# openSX70-dongle_v4-push-MINI.net
KiCad netlist of a schematic drawn in EAGLE
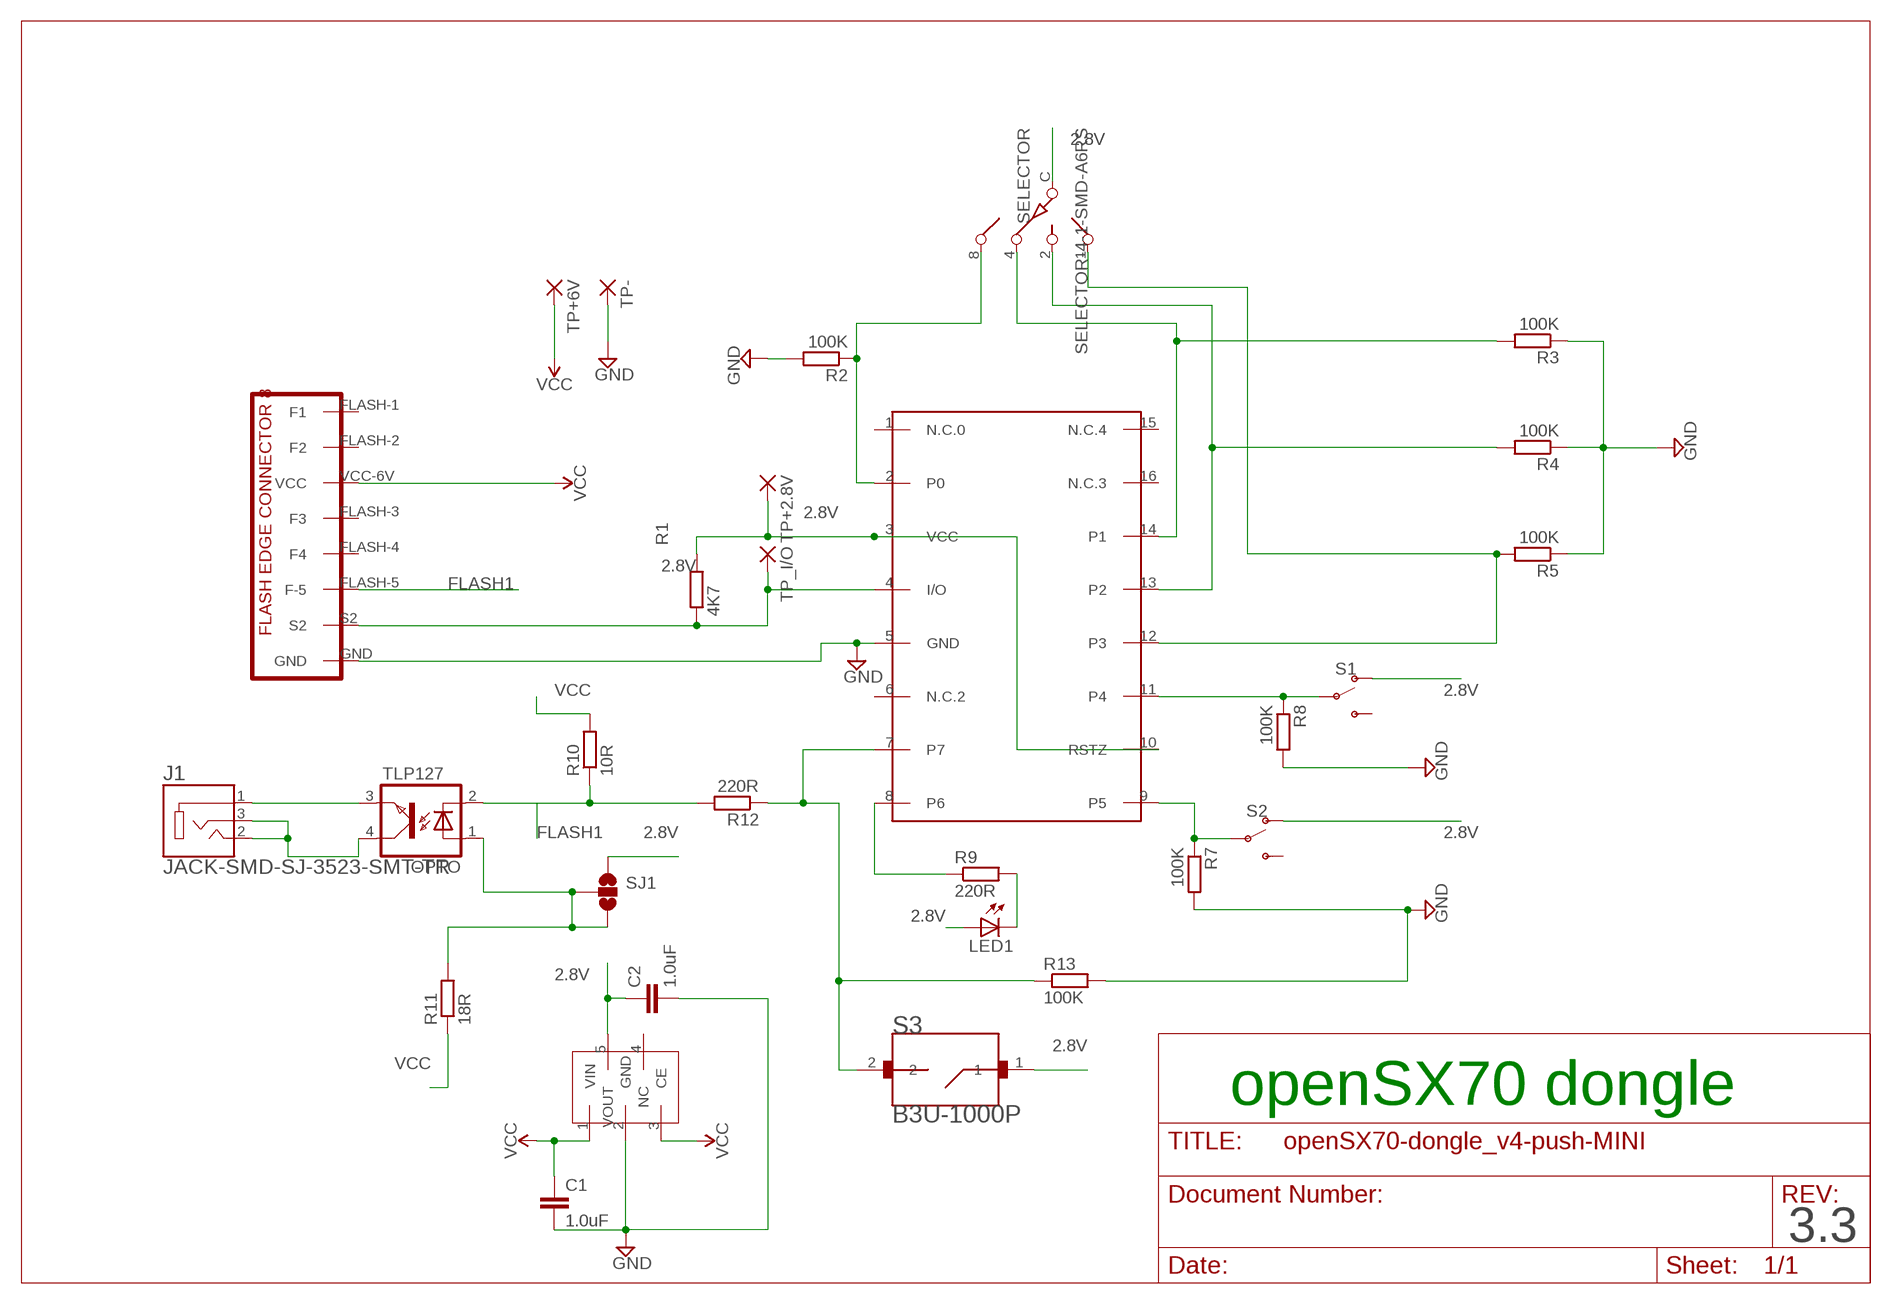
[diagram p0: schematic, sheet 1]

(export (version "E")
  (design (tool "Eeschema 10.0.6"))
  (components
    (comp (ref "C1")
      (value "1.0uF")
      (footprint "eagle-import:C0603")
      (libsource (lib "eagle-import") (part "C-EUC0603"))
    )
    (comp (ref "C2")
      (value "1.0uF")
      (footprint "eagle-import:C0603")
      (libsource (lib "eagle-import") (part "C-EUC0603"))
    )
    (comp (ref "DS2408")
      (value "DS2408")
      (footprint "eagle-import:SO16")
      (libsource (lib "eagle-import") (part "DS2408"))
    )
    (comp (ref "J1")
      (value "JACK-SMD-SJ-3523-SMT-TR")
      (footprint "eagle-import:CUI_SJ-3523-SMT-TR")
      (fields (field (name "MF") "CUI Inc.") (field (name "MP") "SJ-3523-SMT-TR"))
      (libsource (lib "eagle-import") (part "JACK-SMD-SJ-3523-SMT-TR"))
    )
    (comp (ref "LED1")
      (value "LED3MM")
      (footprint "eagle-import:LED3MM")
      (libsource (lib "eagle-import") (part "LED3MM"))
    )
    (comp (ref "OPTO")
      (value "TLP127")
      (footprint "eagle-import:SO-4")
      (libsource (lib "eagle-import") (part "TLP127"))
    )
    (comp (ref "R1")
      (value "4K7")
      (footprint "eagle-import:R0603")
      (libsource (lib "eagle-import") (part "R-EU_R0603"))
    )
    (comp (ref "R2")
      (value "100K")
      (footprint "eagle-import:R0603")
      (libsource (lib "eagle-import") (part "R-EU_R0603"))
    )
    (comp (ref "R3")
      (value "100K")
      (footprint "eagle-import:R0603")
      (libsource (lib "eagle-import") (part "R-EU_R0603"))
    )
    (comp (ref "R4")
      (value "100K")
      (footprint "eagle-import:R0603")
      (libsource (lib "eagle-import") (part "R-EU_R0603"))
    )
    (comp (ref "R5")
      (value "100K")
      (footprint "eagle-import:R0603")
      (libsource (lib "eagle-import") (part "R-EU_R0603"))
    )
    (comp (ref "R7")
      (value "100K")
      (footprint "eagle-import:R0603")
      (libsource (lib "eagle-import") (part "R-EU_R0603"))
    )
    (comp (ref "R8")
      (value "100K")
      (footprint "eagle-import:R0603")
      (libsource (lib "eagle-import") (part "R-EU_R0603"))
    )
    (comp (ref "R9")
      (value "220R")
      (footprint "eagle-import:R0603")
      (libsource (lib "eagle-import") (part "R-EU_R0603"))
    )
    (comp (ref "R10")
      (value "10R")
      (footprint "eagle-import:R0603")
      (libsource (lib "eagle-import") (part "resistor_348_R-EU_R0603"))
    )
    (comp (ref "R11")
      (value "18R")
      (footprint "eagle-import:R0603")
      (libsource (lib "eagle-import") (part "resistor_348_R-EU_R0603"))
    )
    (comp (ref "R12")
      (value "220R")
      (footprint "eagle-import:R0603")
      (libsource (lib "eagle-import") (part "R-EU_R0603"))
    )
    (comp (ref "R13")
      (value "100K")
      (footprint "eagle-import:R0603")
      (libsource (lib "eagle-import") (part "R-EU_R0603"))
    )
    (comp (ref "REG")
      (value "NCP4688")
      (footprint "eagle-import:SOT-23-5")
      (libsource (lib "eagle-import") (part "NCP4688"))
    )
    (comp (ref "S1")
      (value "SWITCH-SPDT-SMD-RIGHT-ANGLE")
      (footprint "eagle-import:SWITCH_SPST_SMD_A")
      (libsource (lib "eagle-import") (part "SWITCH-SPDT-SMD-RIGHT-ANGLE"))
    )
    (comp (ref "S2")
      (value "SWITCH-SPDT-SMD-RIGHT-ANGLE")
      (footprint "eagle-import:SWITCH_SPST_SMD_A")
      (libsource (lib "eagle-import") (part "SWITCH-SPDT-SMD-RIGHT-ANGLE"))
    )
    (comp (ref "S3")
      (value "B3U-1000P")
      (footprint "eagle-import:SW_B3U-1000P")
      (fields (field (name "MANUFACTURER") "Omron"))
      (libsource (lib "eagle-import") (part "B3U-1000P"))
    )
    (comp (ref "SELECTOR")
      (value "SELECTOR-4-1-SMD-A6RS")
      (footprint "eagle-import:A6RS-161RS")
      (libsource (lib "eagle-import") (part "SELECTOR-4-1-SMD-A6RS"))
    )
    (comp (ref "SJ1")
      (value "SOLDERJUMPER_2WAYS")
      (footprint "eagle-import:SJ_3")
      (libsource (lib "eagle-import") (part "SOLDERJUMPER_2WAYS"))
    )
    (comp (ref "TP+2.8V")
      (value "SMD2")
      (footprint "eagle-import:SMD1,27-2,54")
      (libsource (lib "eagle-import") (part "SMD2"))
    )
    (comp (ref "TP+6V")
      (value "SMD2")
      (footprint "eagle-import:SMD1,27-2,54")
      (libsource (lib "eagle-import") (part "SMD2"))
    )
    (comp (ref "TP-")
      (value "SMD2")
      (footprint "eagle-import:SMD1,27-2,54")
      (libsource (lib "eagle-import") (part "SMD2"))
    )
    (comp (ref "TP_I/O")
      (value "SMD2")
      (footprint "eagle-import:SMD1,27-2,54")
      (libsource (lib "eagle-import") (part "SMD2"))
    )
    (comp (ref "U$2")
      (value "SX70-FLASH-EDGE8-MALE-PROPER")
      (footprint "eagle-import:SX70-FLASH-EDGE8")
      (libsource (lib "eagle-import") (part "SX70-FLASH-EDGE8-MALE-PROPER"))
    )
  )
  (nets
    (net (code "1") (name "/2.8V") (class "Default")
      (node (ref "C2") (pin "1") (pinfunction "1_1") (pintype "passive"))
      (node (ref "DS2408") (pin "10") (pinfunction "RSTZ_10") (pintype "bidirectional"))
      (node (ref "DS2408") (pin "3") (pinfunction "VCC_3") (pintype "bidirectional"))
      (node (ref "LED1") (pin "A") (pinfunction "A_A") (pintype "passive"))
      (node (ref "R1") (pin "2") (pinfunction "2_2") (pintype "passive"))
      (node (ref "REG") (pin "5") (pinfunction "VOUT_5") (pintype "bidirectional"))
      (node (ref "S1") (pin "1") (pinfunction "O_1") (pintype "passive"))
      (node (ref "S2") (pin "1") (pinfunction "O_1") (pintype "passive"))
      (node (ref "S3") (pin "1") (pinfunction "1_1") (pintype "passive"))
      (node (ref "SELECTOR") (pin "C") (pinfunction "C_C") (pintype "passive"))
      (node (ref "SJ1") (pin "1") (pinfunction "1_1") (pintype "passive"))
      (node (ref "TP+2.8V") (pin "1") (pinfunction "P_1") (pintype "passive"))
    )
    (net (code "2") (name "/FLASH1") (class "Default")
      (node (ref "OPTO") (pin "1") (pinfunction "A_1") (pintype "passive"))
      (node (ref "OPTO") (pin "2") (pinfunction "C_2") (pintype "passive"))
      (node (ref "R10") (pin "1") (pinfunction "1_1") (pintype "passive"))
      (node (ref "R11") (pin "2") (pinfunction "2_2") (pintype "passive"))
      (node (ref "R12") (pin "2") (pinfunction "2_2") (pintype "passive"))
      (node (ref "SJ1") (pin "2") (pinfunction "2_2") (pintype "passive"))
      (node (ref "SJ1") (pin "3") (pinfunction "3_3") (pintype "passive"))
      (node (ref "U$2") (pin "FLASH-5") (pinfunction "F-5_FLASH-5") (pintype "bidirectional"))
    )
    (net (code "3") (name "GND") (class "Default")
      (node (ref "C1") (pin "2") (pinfunction "2_2") (pintype "passive"))
      (node (ref "C2") (pin "2") (pinfunction "2_2") (pintype "passive"))
      (node (ref "DS2408") (pin "5") (pinfunction "GND_5") (pintype "bidirectional"))
      (node (ref "R13") (pin "2") (pinfunction "2_2") (pintype "passive"))
      (node (ref "R2") (pin "2") (pinfunction "2_2") (pintype "passive"))
      (node (ref "R3") (pin "1") (pinfunction "1_1") (pintype "passive"))
      (node (ref "R4") (pin "1") (pinfunction "1_1") (pintype "passive"))
      (node (ref "R5") (pin "1") (pinfunction "1_1") (pintype "passive"))
      (node (ref "R7") (pin "2") (pinfunction "2_2") (pintype "passive"))
      (node (ref "R8") (pin "2") (pinfunction "2_2") (pintype "passive"))
      (node (ref "REG") (pin "2") (pinfunction "GND_2") (pintype "bidirectional"))
      (node (ref "TP-") (pin "1") (pinfunction "P_1") (pintype "passive"))
      (node (ref "U$2") (pin "GND") (pinfunction "GND_GND") (pintype "bidirectional"))
    )
    (net (code "4") (name "Net-(DS2408-I{slash}O)") (class "Default")
      (node (ref "DS2408") (pin "4") (pinfunction "I/O_4") (pintype "bidirectional"))
      (node (ref "R1") (pin "1") (pinfunction "1_1") (pintype "passive"))
      (node (ref "TP_I/O") (pin "1") (pinfunction "P_1") (pintype "passive"))
      (node (ref "U$2") (pin "S2") (pinfunction "S2_S2") (pintype "bidirectional"))
    )
    (net (code "5") (name "Net-(DS2408-P0)") (class "Default")
      (node (ref "DS2408") (pin "2") (pinfunction "P0_2") (pintype "bidirectional"))
      (node (ref "R2") (pin "1") (pinfunction "1_1") (pintype "passive"))
      (node (ref "SELECTOR") (pin "8") (pinfunction "8_8") (pintype "passive"))
    )
    (net (code "6") (name "Net-(DS2408-P1)") (class "Default")
      (node (ref "DS2408") (pin "14") (pinfunction "P1_14") (pintype "bidirectional"))
      (node (ref "R3") (pin "2") (pinfunction "2_2") (pintype "passive"))
      (node (ref "SELECTOR") (pin "4") (pinfunction "4_4") (pintype "passive"))
    )
    (net (code "7") (name "Net-(DS2408-P2)") (class "Default")
      (node (ref "DS2408") (pin "13") (pinfunction "P2_13") (pintype "bidirectional"))
      (node (ref "R4") (pin "2") (pinfunction "2_2") (pintype "passive"))
      (node (ref "SELECTOR") (pin "2") (pinfunction "2_2") (pintype "passive"))
    )
    (net (code "8") (name "Net-(DS2408-P3)") (class "Default")
      (node (ref "DS2408") (pin "12") (pinfunction "P3_12") (pintype "bidirectional"))
      (node (ref "R5") (pin "2") (pinfunction "2_2") (pintype "passive"))
      (node (ref "SELECTOR") (pin "1") (pinfunction "1_1") (pintype "passive"))
    )
    (net (code "9") (name "Net-(DS2408-P4)") (class "Default")
      (node (ref "DS2408") (pin "11") (pinfunction "P4_11") (pintype "bidirectional"))
      (node (ref "R8") (pin "1") (pinfunction "1_1") (pintype "passive"))
      (node (ref "S1") (pin "2") (pinfunction "P_2") (pintype "passive"))
    )
    (net (code "10") (name "Net-(DS2408-P5)") (class "Default")
      (node (ref "DS2408") (pin "9") (pinfunction "P5_9") (pintype "bidirectional"))
      (node (ref "R7") (pin "1") (pinfunction "1_1") (pintype "passive"))
      (node (ref "S2") (pin "2") (pinfunction "P_2") (pintype "passive"))
    )
    (net (code "11") (name "Net-(DS2408-P6)") (class "Default")
      (node (ref "DS2408") (pin "8") (pinfunction "P6_8") (pintype "bidirectional"))
      (node (ref "R9") (pin "1") (pinfunction "1_1") (pintype "passive"))
    )
    (net (code "12") (name "Net-(DS2408-P7)") (class "Default")
      (node (ref "DS2408") (pin "7") (pinfunction "P7_7") (pintype "bidirectional"))
      (node (ref "R12") (pin "1") (pinfunction "1_1") (pintype "passive"))
      (node (ref "R13") (pin "1") (pinfunction "1_1") (pintype "passive"))
      (node (ref "S3") (pin "2") (pinfunction "2_2") (pintype "passive"))
    )
    (net (code "13") (name "Net-(LED1-C)") (class "Default")
      (node (ref "LED1") (pin "K") (pinfunction "C_K") (pintype "passive"))
      (node (ref "R9") (pin "2") (pinfunction "2_2") (pintype "passive"))
    )
    (net (code "14") (name "Net-(OPTO-COL)") (class "Default")
      (node (ref "J1") (pin "2") (pinfunction "2_2") (pintype "passive"))
      (node (ref "J1") (pin "3") (pinfunction "3_3") (pintype "passive"))
      (node (ref "OPTO") (pin "4") (pinfunction "COL_4") (pintype "passive"))
    )
    (net (code "15") (name "Net-(OPTO-EMIT)") (class "Default")
      (node (ref "J1") (pin "1") (pinfunction "1_1") (pintype "passive"))
      (node (ref "OPTO") (pin "3") (pinfunction "EMIT_3") (pintype "passive"))
    )
    (net (code "16") (name "VCC") (class "Default")
      (node (ref "C1") (pin "1") (pinfunction "1_1") (pintype "passive"))
      (node (ref "R10") (pin "2") (pinfunction "2_2") (pintype "passive"))
      (node (ref "R11") (pin "1") (pinfunction "1_1") (pintype "passive"))
      (node (ref "REG") (pin "1") (pinfunction "VIN_1") (pintype "bidirectional"))
      (node (ref "REG") (pin "3") (pinfunction "CE_3") (pintype "bidirectional"))
      (node (ref "TP+6V") (pin "1") (pinfunction "P_1") (pintype "passive"))
      (node (ref "U$2") (pin "VCC-6V") (pinfunction "VCC_VCC-6V") (pintype "bidirectional"))
    )
    (net (code "17") (name "unconnected-(DS2408-N.C.0-Pad1)") (class "Default")
      (node (ref "DS2408") (pin "1") (pinfunction "N.C.0_1") (pintype "bidirectional"))
    )
    (net (code "18") (name "unconnected-(DS2408-N.C.2-Pad6)") (class "Default")
      (node (ref "DS2408") (pin "6") (pinfunction "N.C.2_6") (pintype "bidirectional"))
    )
    (net (code "19") (name "unconnected-(DS2408-N.C.3-Pad16)") (class "Default")
      (node (ref "DS2408") (pin "16") (pinfunction "N.C.3_16") (pintype "bidirectional"))
    )
    (net (code "20") (name "unconnected-(DS2408-N.C.4-Pad15)") (class "Default")
      (node (ref "DS2408") (pin "15") (pinfunction "N.C.4_15") (pintype "bidirectional"))
    )
    (net (code "21") (name "unconnected-(REG-NC-Pad4)") (class "Default")
      (node (ref "REG") (pin "4") (pinfunction "NC_4") (pintype "bidirectional"))
    )
    (net (code "22") (name "unconnected-(S1-S-Pad3)") (class "Default")
      (node (ref "S1") (pin "3") (pinfunction "S_3") (pintype "passive"))
    )
    (net (code "23") (name "unconnected-(S2-S-Pad3)") (class "Default")
      (node (ref "S2") (pin "3") (pinfunction "S_3") (pintype "passive"))
    )
    (net (code "24") (name "unconnected-(U$2-F1-PadFLASH-1)") (class "Default")
      (node (ref "U$2") (pin "FLASH-1") (pinfunction "F1_FLASH-1") (pintype "bidirectional"))
    )
    (net (code "25") (name "unconnected-(U$2-F2-PadFLASH-2)") (class "Default")
      (node (ref "U$2") (pin "FLASH-2") (pinfunction "F2_FLASH-2") (pintype "bidirectional"))
    )
    (net (code "26") (name "unconnected-(U$2-F3-PadFLASH-3)") (class "Default")
      (node (ref "U$2") (pin "FLASH-3") (pinfunction "F3_FLASH-3") (pintype "bidirectional"))
    )
    (net (code "27") (name "unconnected-(U$2-F4-PadFLASH-4)") (class "Default")
      (node (ref "U$2") (pin "FLASH-4") (pinfunction "F4_FLASH-4") (pintype "bidirectional"))
    )
  )
)
